# rs485board.net
KiCad netlist of a schematic drawn in EAGLE
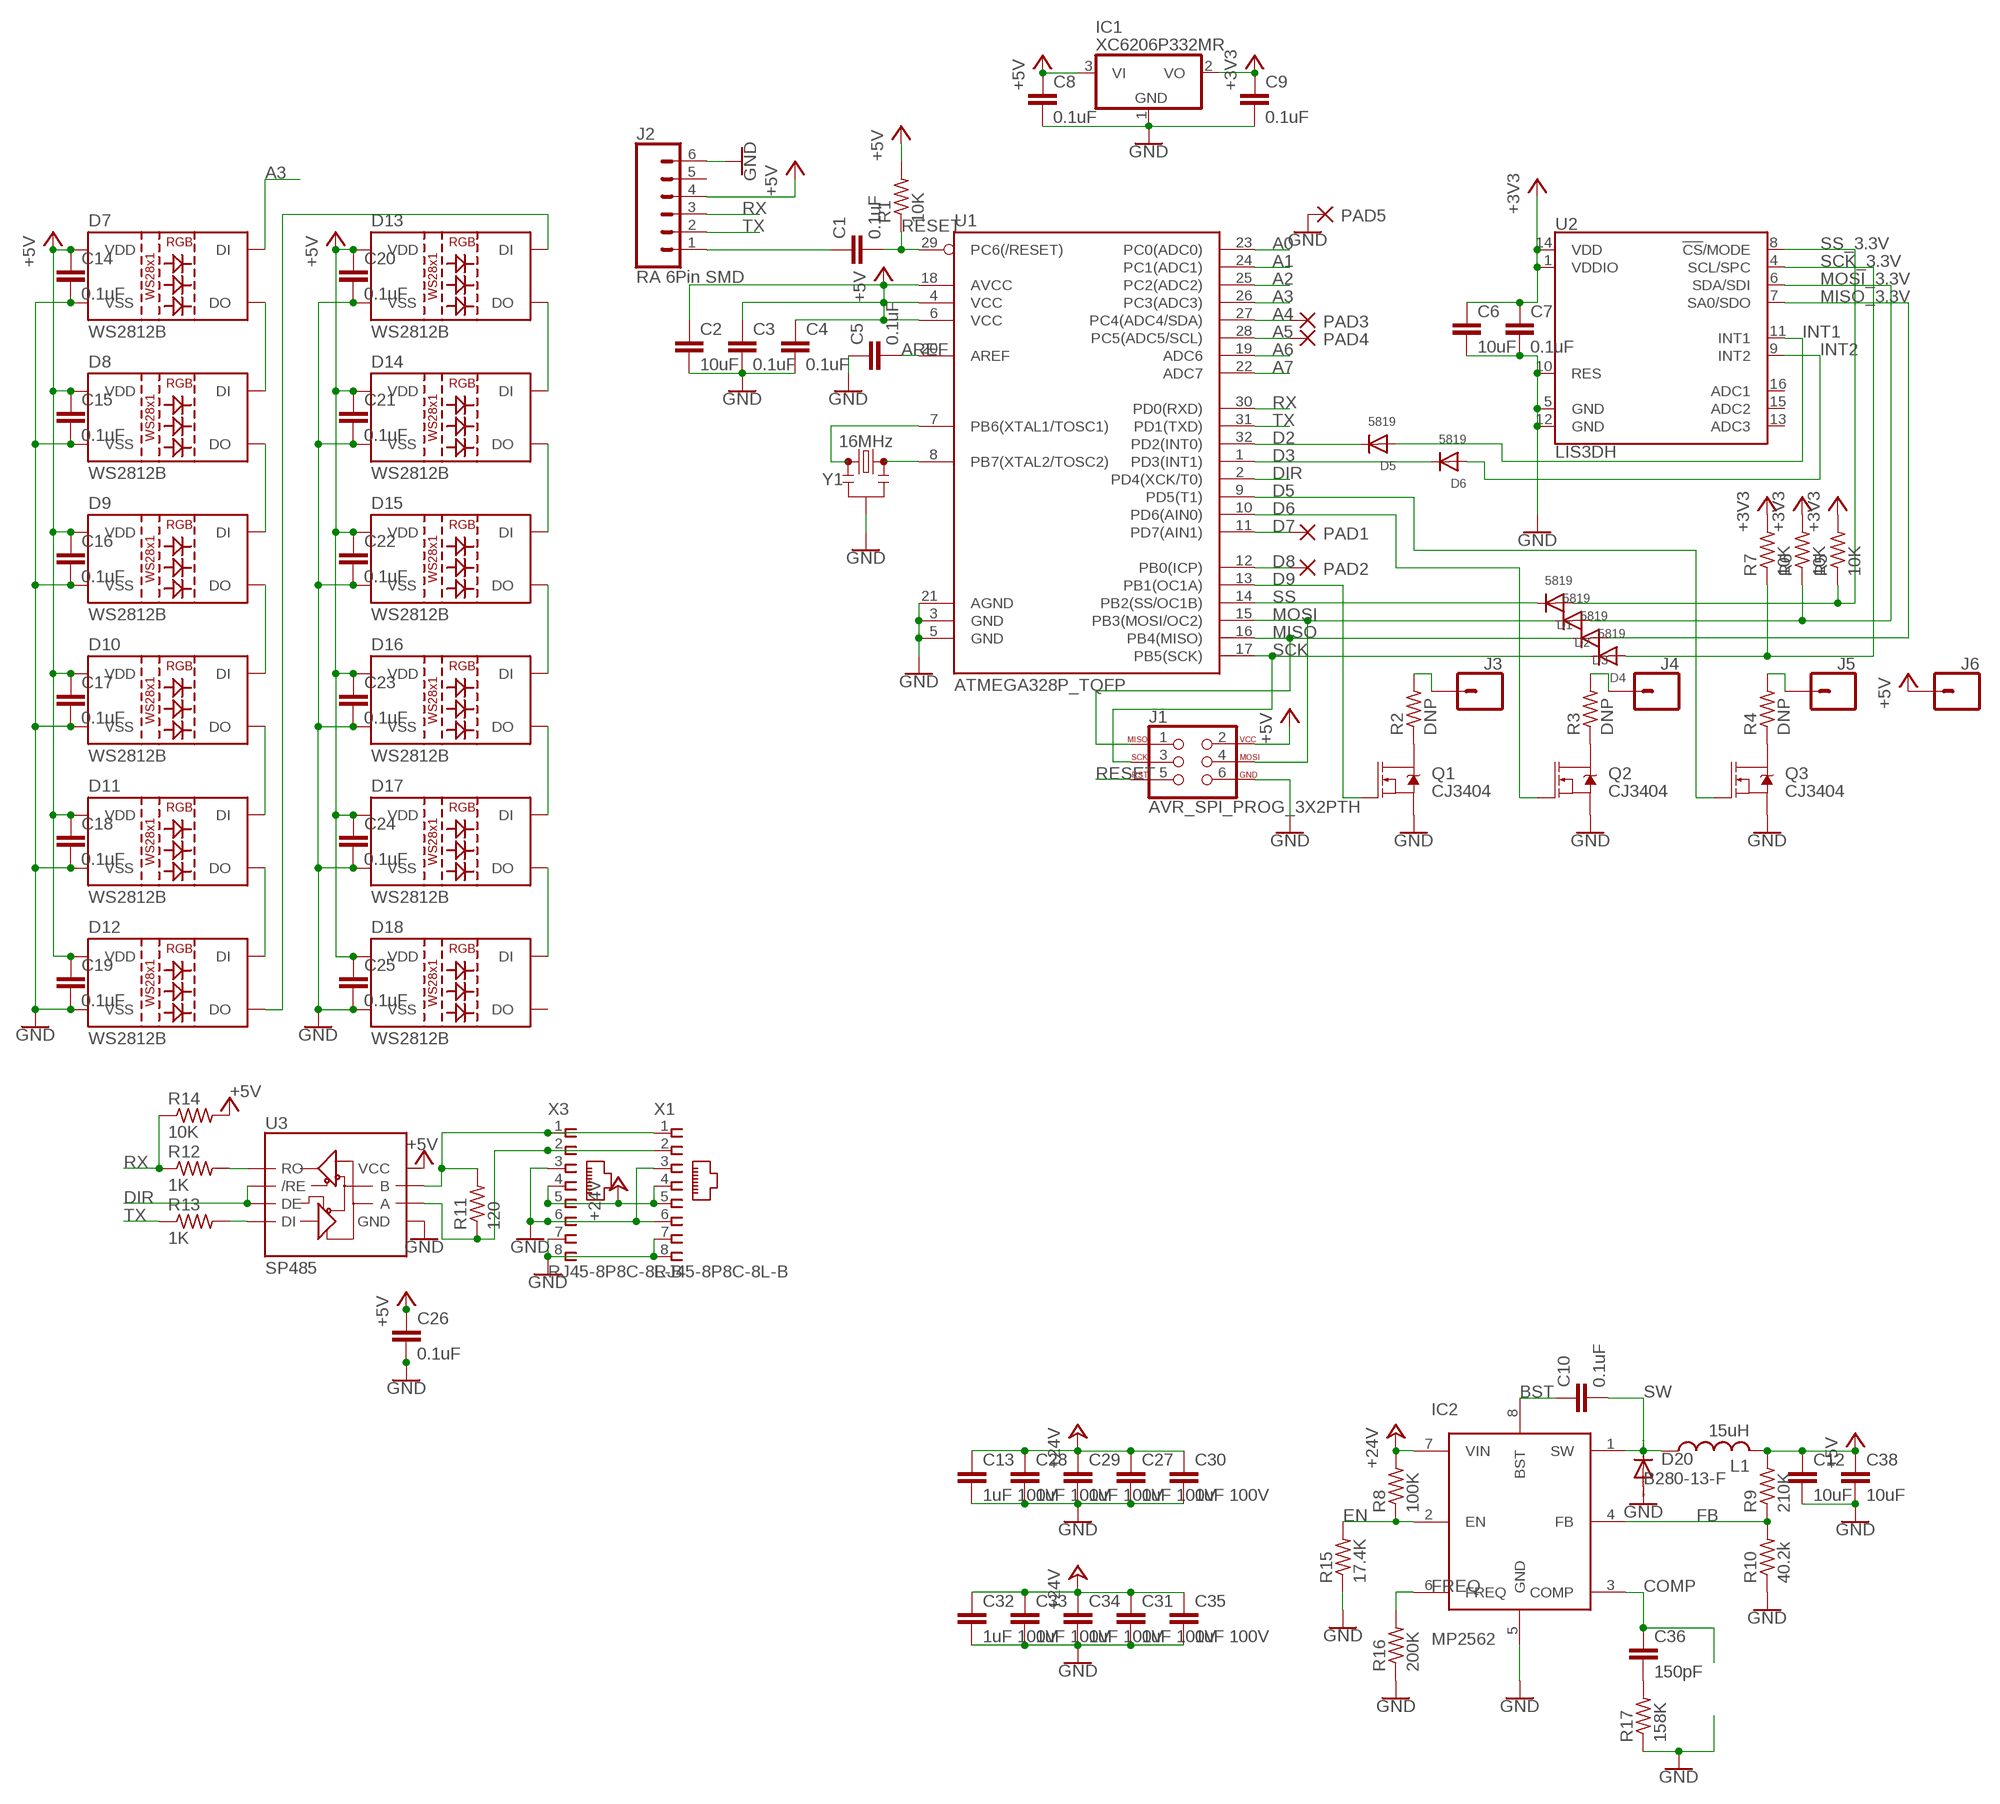
[diagram p0: schematic, sheet 1]

(export (version "E")
  (design (tool "Eeschema 10.0.6"))
  (components
    (comp (ref "C1")
      (value "0.1uF")
      (footprint "eagle-import:C0805K")
      (libsource (lib "eagle-import") (part "C-EUC0805K"))
    )
    (comp (ref "C2")
      (value "10uF")
      (footprint "eagle-import:C0805K")
      (libsource (lib "eagle-import") (part "C-EUC0805K"))
    )
    (comp (ref "C3")
      (value "0.1uF")
      (footprint "eagle-import:C0805K")
      (libsource (lib "eagle-import") (part "C-EUC0805K"))
    )
    (comp (ref "C4")
      (value "0.1uF")
      (footprint "eagle-import:C0805K")
      (libsource (lib "eagle-import") (part "C-EUC0805K"))
    )
    (comp (ref "C5")
      (value "0.1uF")
      (footprint "eagle-import:C0805K")
      (libsource (lib "eagle-import") (part "C-EUC0805K"))
    )
    (comp (ref "C6")
      (value "10uF")
      (footprint "eagle-import:C0805K")
      (libsource (lib "eagle-import") (part "C-EUC0805K"))
    )
    (comp (ref "C7")
      (value "0.1uF")
      (footprint "eagle-import:C0805K")
      (libsource (lib "eagle-import") (part "C-EUC0805K"))
    )
    (comp (ref "C8")
      (value "0.1uF")
      (footprint "eagle-import:C0805K")
      (libsource (lib "eagle-import") (part "C-EUC0805K"))
    )
    (comp (ref "C9")
      (value "0.1uF")
      (footprint "eagle-import:C0805K")
      (libsource (lib "eagle-import") (part "C-EUC0805K"))
    )
    (comp (ref "C10")
      (value "0.1uF")
      (footprint "eagle-import:C0805K")
      (libsource (lib "eagle-import") (part "C-EUC0805K"))
    )
    (comp (ref "C12")
      (value "10uF")
      (footprint "eagle-import:C0805K")
      (libsource (lib "eagle-import") (part "C-EUC0805K"))
    )
    (comp (ref "C13")
      (value "1uF 100V")
      (footprint "eagle-import:1206")
      (libsource (lib "eagle-import") (part "10UF-1206-6.3V-20%"))
    )
    (comp (ref "C14")
      (value "0.1uF")
      (footprint "eagle-import:C0805K")
      (libsource (lib "eagle-import") (part "C-EUC0805K"))
    )
    (comp (ref "C15")
      (value "0.1uF")
      (footprint "eagle-import:C0805K")
      (libsource (lib "eagle-import") (part "C-EUC0805K"))
    )
    (comp (ref "C16")
      (value "0.1uF")
      (footprint "eagle-import:C0805K")
      (libsource (lib "eagle-import") (part "C-EUC0805K"))
    )
    (comp (ref "C17")
      (value "0.1uF")
      (footprint "eagle-import:C0805K")
      (libsource (lib "eagle-import") (part "C-EUC0805K"))
    )
    (comp (ref "C18")
      (value "0.1uF")
      (footprint "eagle-import:C0805K")
      (libsource (lib "eagle-import") (part "C-EUC0805K"))
    )
    (comp (ref "C19")
      (value "0.1uF")
      (footprint "eagle-import:C0805K")
      (libsource (lib "eagle-import") (part "C-EUC0805K"))
    )
    (comp (ref "C20")
      (value "0.1uF")
      (footprint "eagle-import:C0805K")
      (libsource (lib "eagle-import") (part "C-EUC0805K"))
    )
    (comp (ref "C21")
      (value "0.1uF")
      (footprint "eagle-import:C0805K")
      (libsource (lib "eagle-import") (part "C-EUC0805K"))
    )
    (comp (ref "C22")
      (value "0.1uF")
      (footprint "eagle-import:C0805K")
      (libsource (lib "eagle-import") (part "C-EUC0805K"))
    )
    (comp (ref "C23")
      (value "0.1uF")
      (footprint "eagle-import:C0805K")
      (libsource (lib "eagle-import") (part "C-EUC0805K"))
    )
    (comp (ref "C24")
      (value "0.1uF")
      (footprint "eagle-import:C0805K")
      (libsource (lib "eagle-import") (part "C-EUC0805K"))
    )
    (comp (ref "C25")
      (value "0.1uF")
      (footprint "eagle-import:C0805K")
      (libsource (lib "eagle-import") (part "C-EUC0805K"))
    )
    (comp (ref "C26")
      (value "0.1uF")
      (footprint "eagle-import:C0805K")
      (libsource (lib "eagle-import") (part "C-EUC0805K"))
    )
    (comp (ref "C27")
      (value "1uF 100V")
      (footprint "eagle-import:1206")
      (libsource (lib "eagle-import") (part "10UF-1206-6.3V-20%"))
    )
    (comp (ref "C28")
      (value "1uF 100V")
      (footprint "eagle-import:1206")
      (libsource (lib "eagle-import") (part "10UF-1206-6.3V-20%"))
    )
    (comp (ref "C29")
      (value "1uF 100V")
      (footprint "eagle-import:1206")
      (libsource (lib "eagle-import") (part "10UF-1206-6.3V-20%"))
    )
    (comp (ref "C30")
      (value "1uF 100V")
      (footprint "eagle-import:1206")
      (libsource (lib "eagle-import") (part "10UF-1206-6.3V-20%"))
    )
    (comp (ref "C31")
      (value "1uF 100V")
      (footprint "eagle-import:1206")
      (libsource (lib "eagle-import") (part "10UF-1206-6.3V-20%"))
    )
    (comp (ref "C32")
      (value "1uF 100V")
      (footprint "eagle-import:1206")
      (libsource (lib "eagle-import") (part "10UF-1206-6.3V-20%"))
    )
    (comp (ref "C33")
      (value "1uF 100V")
      (footprint "eagle-import:1206")
      (libsource (lib "eagle-import") (part "10UF-1206-6.3V-20%"))
    )
    (comp (ref "C34")
      (value "1uF 100V")
      (footprint "eagle-import:1206")
      (libsource (lib "eagle-import") (part "10UF-1206-6.3V-20%"))
    )
    (comp (ref "C35")
      (value "1uF 100V")
      (footprint "eagle-import:1206")
      (libsource (lib "eagle-import") (part "10UF-1206-6.3V-20%"))
    )
    (comp (ref "C36")
      (value "150pF")
      (footprint "eagle-import:C0805K")
      (libsource (lib "eagle-import") (part "C-EUC0805K"))
    )
    (comp (ref "C38")
      (value "10uF")
      (footprint "eagle-import:C0805K")
      (libsource (lib "eagle-import") (part "C-EUC0805K"))
    )
    (comp (ref "D1")
      (value "5819")
      (footprint "eagle-import:SOD-123")
      (libsource (lib "eagle-import") (part "DIODESOD-123"))
    )
    (comp (ref "D2")
      (value "5819")
      (footprint "eagle-import:SOD-123")
      (libsource (lib "eagle-import") (part "DIODESOD-123"))
    )
    (comp (ref "D3")
      (value "5819")
      (footprint "eagle-import:SOD-123")
      (libsource (lib "eagle-import") (part "DIODESOD-123"))
    )
    (comp (ref "D4")
      (value "5819")
      (footprint "eagle-import:SOD-123")
      (libsource (lib "eagle-import") (part "DIODESOD-123"))
    )
    (comp (ref "D5")
      (value "5819")
      (footprint "eagle-import:SOD-123")
      (libsource (lib "eagle-import") (part "DIODESOD-123"))
    )
    (comp (ref "D6")
      (value "5819")
      (footprint "eagle-import:SOD-123")
      (libsource (lib "eagle-import") (part "DIODESOD-123"))
    )
    (comp (ref "D7")
      (value "WS2812B")
      (footprint "eagle-import:WS2812B")
      (libsource (lib "eagle-import") (part "WS2812B"))
    )
    (comp (ref "D8")
      (value "WS2812B")
      (footprint "eagle-import:WS2812B")
      (libsource (lib "eagle-import") (part "WS2812B"))
    )
    (comp (ref "D9")
      (value "WS2812B")
      (footprint "eagle-import:WS2812B")
      (libsource (lib "eagle-import") (part "WS2812B"))
    )
    (comp (ref "D10")
      (value "WS2812B")
      (footprint "eagle-import:WS2812B")
      (libsource (lib "eagle-import") (part "WS2812B"))
    )
    (comp (ref "D11")
      (value "WS2812B")
      (footprint "eagle-import:WS2812B")
      (libsource (lib "eagle-import") (part "WS2812B"))
    )
    (comp (ref "D12")
      (value "WS2812B")
      (footprint "eagle-import:WS2812B")
      (libsource (lib "eagle-import") (part "WS2812B"))
    )
    (comp (ref "D13")
      (value "WS2812B")
      (footprint "eagle-import:WS2812B")
      (libsource (lib "eagle-import") (part "WS2812B"))
    )
    (comp (ref "D14")
      (value "WS2812B")
      (footprint "eagle-import:WS2812B")
      (libsource (lib "eagle-import") (part "WS2812B"))
    )
    (comp (ref "D15")
      (value "WS2812B")
      (footprint "eagle-import:WS2812B")
      (libsource (lib "eagle-import") (part "WS2812B"))
    )
    (comp (ref "D16")
      (value "WS2812B")
      (footprint "eagle-import:WS2812B")
      (libsource (lib "eagle-import") (part "WS2812B"))
    )
    (comp (ref "D17")
      (value "WS2812B")
      (footprint "eagle-import:WS2812B")
      (libsource (lib "eagle-import") (part "WS2812B"))
    )
    (comp (ref "D18")
      (value "WS2812B")
      (footprint "eagle-import:WS2812B")
      (libsource (lib "eagle-import") (part "WS2812B"))
    )
    (comp (ref "D20")
      (value "B280-13-F")
      (footprint "eagle-import:DO214AA")
      (libsource (lib "eagle-import") (part "DIODE-DO214AA"))
    )
    (comp (ref "IC1")
      (value "XC6206P332MR")
      (footprint "eagle-import:SOT23")
      (libsource (lib "eagle-import") (part "MCP1703CB"))
    )
    (comp (ref "IC2")
      (value "MP2562")
      (footprint "eagle-import:SO08")
      (libsource (lib "eagle-import") (part "MP2562"))
    )
    (comp (ref "J1")
      (value "AVR_SPI_PROG_3X2PTH")
      (footprint "eagle-import:2X3")
      (libsource (lib "eagle-import") (part "AVR_SPI_PROG_3X2PTH"))
    )
    (comp (ref "J2")
      (value "RA 6Pin SMD")
      (footprint "eagle-import:1X06-SMD_RA_MALE")
      (libsource (lib "eagle-import") (part "CONN_06SMD"))
    )
    (comp (ref "J3")
      (value "CONN_01")
      (footprint "eagle-import:1X01")
      (libsource (lib "eagle-import") (part "CONN_01"))
    )
    (comp (ref "J4")
      (value "CONN_01")
      (footprint "eagle-import:1X01")
      (libsource (lib "eagle-import") (part "CONN_01"))
    )
    (comp (ref "J5")
      (value "CONN_01")
      (footprint "eagle-import:1X01")
      (libsource (lib "eagle-import") (part "CONN_01"))
    )
    (comp (ref "J6")
      (value "CONN_01")
      (footprint "eagle-import:1X01")
      (libsource (lib "eagle-import") (part "CONN_01"))
    )
    (comp (ref "L1")
      (value "15uH")
      (footprint "eagle-import:SLF12575")
      (libsource (lib "eagle-import") (part "SLF12575T"))
    )
    (comp (ref "PAD1")
      (value "1,6/0,8")
      (footprint "eagle-import:1,6_0,8")
      (libsource (lib "eagle-import") (part "1,6/0,8"))
    )
    (comp (ref "PAD2")
      (value "1,6/0,8")
      (footprint "eagle-import:1,6_0,8")
      (libsource (lib "eagle-import") (part "1,6/0,8"))
    )
    (comp (ref "PAD3")
      (value "1,6/0,8")
      (footprint "eagle-import:1,6_0,8")
      (libsource (lib "eagle-import") (part "1,6/0,8"))
    )
    (comp (ref "PAD4")
      (value "1,6/0,8")
      (footprint "eagle-import:1,6_0,8")
      (libsource (lib "eagle-import") (part "1,6/0,8"))
    )
    (comp (ref "PAD5")
      (value "1,6/0,8")
      (footprint "eagle-import:1,6_0,8")
      (libsource (lib "eagle-import") (part "1,6/0,8"))
    )
    (comp (ref "Q1")
      (value "CJ3404")
      (footprint "eagle-import:SOT23-3")
      (libsource (lib "eagle-import") (part "MOSFET-NCH-AO3404A"))
    )
    (comp (ref "Q2")
      (value "CJ3404")
      (footprint "eagle-import:SOT23-3")
      (libsource (lib "eagle-import") (part "MOSFET-NCH-AO3404A"))
    )
    (comp (ref "Q3")
      (value "CJ3404")
      (footprint "eagle-import:SOT23-3")
      (libsource (lib "eagle-import") (part "MOSFET-NCH-AO3404A"))
    )
    (comp (ref "R1")
      (value "10K")
      (footprint "eagle-import:R0805")
      (libsource (lib "eagle-import") (part "R-US_R0805"))
    )
    (comp (ref "R2")
      (value "DNP")
      (footprint "eagle-import:R0805")
      (libsource (lib "eagle-import") (part "R-US_R0805"))
    )
    (comp (ref "R3")
      (value "DNP")
      (footprint "eagle-import:R0805")
      (libsource (lib "eagle-import") (part "R-US_R0805"))
    )
    (comp (ref "R4")
      (value "DNP")
      (footprint "eagle-import:R0805")
      (libsource (lib "eagle-import") (part "R-US_R0805"))
    )
    (comp (ref "R5")
      (value "10K")
      (footprint "eagle-import:R0805")
      (libsource (lib "eagle-import") (part "R-US_R0805"))
    )
    (comp (ref "R6")
      (value "10K")
      (footprint "eagle-import:R0805")
      (libsource (lib "eagle-import") (part "R-US_R0805"))
    )
    (comp (ref "R7")
      (value "10K")
      (footprint "eagle-import:R0805")
      (libsource (lib "eagle-import") (part "R-US_R0805"))
    )
    (comp (ref "R8")
      (value "100K")
      (footprint "eagle-import:R0805")
      (libsource (lib "eagle-import") (part "R-US_R0805"))
    )
    (comp (ref "R9")
      (value "210K")
      (footprint "eagle-import:R0805")
      (libsource (lib "eagle-import") (part "R-US_R0805"))
    )
    (comp (ref "R10")
      (value "40.2k")
      (footprint "eagle-import:R0805")
      (libsource (lib "eagle-import") (part "R-US_R0805"))
    )
    (comp (ref "R11")
      (value "120")
      (footprint "eagle-import:R0805")
      (libsource (lib "eagle-import") (part "R-US_R0805"))
    )
    (comp (ref "R12")
      (value "1K")
      (footprint "eagle-import:R0805")
      (libsource (lib "eagle-import") (part "R-US_R0805"))
    )
    (comp (ref "R13")
      (value "1K")
      (footprint "eagle-import:R0805")
      (libsource (lib "eagle-import") (part "R-US_R0805"))
    )
    (comp (ref "R14")
      (value "10K")
      (footprint "eagle-import:R0805")
      (libsource (lib "eagle-import") (part "R-US_R0805"))
    )
    (comp (ref "R15")
      (value "17.4K")
      (footprint "eagle-import:R0805")
      (libsource (lib "eagle-import") (part "R-US_R0805"))
    )
    (comp (ref "R16")
      (value "200K")
      (footprint "eagle-import:R0805")
      (libsource (lib "eagle-import") (part "R-US_R0805"))
    )
    (comp (ref "R17")
      (value "158K")
      (footprint "eagle-import:R0805")
      (libsource (lib "eagle-import") (part "R-US_R0805"))
    )
    (comp (ref "U1")
      (value "ATMEGA328P_TQFP")
      (footprint "eagle-import:TQFP32-08")
      (libsource (lib "eagle-import") (part "ATMEGA328P_TQFP"))
    )
    (comp (ref "U2")
      (value "LIS3DH")
      (footprint "eagle-import:LGA-16-3X3")
      (libsource (lib "eagle-import") (part "LIS3DH"))
    )
    (comp (ref "U3")
      (value "SP485")
      (footprint "eagle-import:SO08")
      (libsource (lib "eagle-import") (part "RS485SOIC"))
    )
    (comp (ref "X1")
      (value "RJ45-8P8C-8L-B")
      (footprint "eagle-import:RJ45-SHIELD-DS1128-S80BP")
      (fields (field (name "MF") "TYCO ELECTRONICS") (field (name "MPN") "RJ45-8L-B"))
      (libsource (lib "eagle-import") (part "RJ45-8P8C-8L-B"))
    )
    (comp (ref "X3")
      (value "RJ45-8P8C-8L-B")
      (footprint "eagle-import:RJ45-SHIELD-DS1128-S80BP")
      (fields (field (name "MF") "TYCO ELECTRONICS") (field (name "MPN") "RJ45-8L-B"))
      (libsource (lib "eagle-import") (part "RJ45-8P8C-8L-B"))
    )
    (comp (ref "Y1")
      (value "16MHz")
      (footprint "eagle-import:RESONATOR-SMD-3.2X1.3")
      (libsource (lib "eagle-import") (part "RESONATOR-16MHZSMD_3.2X1.3"))
    )
  )
  (nets
    (net (code "1") (name "+3V3") (class "Default")
      (node (ref "C6") (pin "1") (pinfunction "1_1") (pintype "passive"))
      (node (ref "C7") (pin "1") (pinfunction "1_1") (pintype "passive"))
      (node (ref "C9") (pin "1") (pinfunction "1_1") (pintype "passive"))
      (node (ref "IC1") (pin "2") (pinfunction "VO_2") (pintype "passive"))
      (node (ref "R5") (pin "2") (pinfunction "2_2") (pintype "passive"))
      (node (ref "R6") (pin "2") (pinfunction "2_2") (pintype "passive"))
      (node (ref "R7") (pin "2") (pinfunction "2_2") (pintype "passive"))
      (node (ref "U2") (pin "1") (pinfunction "VDDIO_1") (pintype "bidirectional"))
      (node (ref "U2") (pin "14") (pinfunction "VDD_14") (pintype "bidirectional"))
    )
    (net (code "2") (name "+5V") (class "Default")
      (node (ref "C12") (pin "1") (pinfunction "1_1") (pintype "passive"))
      (node (ref "C14") (pin "1") (pinfunction "1_1") (pintype "passive"))
      (node (ref "C15") (pin "1") (pinfunction "1_1") (pintype "passive"))
      (node (ref "C16") (pin "1") (pinfunction "1_1") (pintype "passive"))
      (node (ref "C17") (pin "1") (pinfunction "1_1") (pintype "passive"))
      (node (ref "C18") (pin "1") (pinfunction "1_1") (pintype "passive"))
      (node (ref "C19") (pin "1") (pinfunction "1_1") (pintype "passive"))
      (node (ref "C2") (pin "1") (pinfunction "1_1") (pintype "passive"))
      (node (ref "C20") (pin "1") (pinfunction "1_1") (pintype "passive"))
      (node (ref "C21") (pin "1") (pinfunction "1_1") (pintype "passive"))
      (node (ref "C22") (pin "1") (pinfunction "1_1") (pintype "passive"))
      (node (ref "C23") (pin "1") (pinfunction "1_1") (pintype "passive"))
      (node (ref "C24") (pin "1") (pinfunction "1_1") (pintype "passive"))
      (node (ref "C25") (pin "1") (pinfunction "1_1") (pintype "passive"))
      (node (ref "C26") (pin "1") (pinfunction "1_1") (pintype "passive"))
      (node (ref "C3") (pin "1") (pinfunction "1_1") (pintype "passive"))
      (node (ref "C38") (pin "1") (pinfunction "1_1") (pintype "passive"))
      (node (ref "C4") (pin "1") (pinfunction "1_1") (pintype "passive"))
      (node (ref "C8") (pin "1") (pinfunction "1_1") (pintype "passive"))
      (node (ref "D10") (pin "1") (pinfunction "VDD_1") (pintype "bidirectional"))
      (node (ref "D11") (pin "1") (pinfunction "VDD_1") (pintype "bidirectional"))
      (node (ref "D12") (pin "1") (pinfunction "VDD_1") (pintype "bidirectional"))
      (node (ref "D13") (pin "1") (pinfunction "VDD_1") (pintype "bidirectional"))
      (node (ref "D14") (pin "1") (pinfunction "VDD_1") (pintype "bidirectional"))
      (node (ref "D15") (pin "1") (pinfunction "VDD_1") (pintype "bidirectional"))
      (node (ref "D16") (pin "1") (pinfunction "VDD_1") (pintype "bidirectional"))
      (node (ref "D17") (pin "1") (pinfunction "VDD_1") (pintype "bidirectional"))
      (node (ref "D18") (pin "1") (pinfunction "VDD_1") (pintype "bidirectional"))
      (node (ref "D7") (pin "1") (pinfunction "VDD_1") (pintype "bidirectional"))
      (node (ref "D8") (pin "1") (pinfunction "VDD_1") (pintype "bidirectional"))
      (node (ref "D9") (pin "1") (pinfunction "VDD_1") (pintype "bidirectional"))
      (node (ref "IC1") (pin "3") (pinfunction "VI_3") (pintype "input"))
      (node (ref "J1") (pin "2") (pinfunction "2_2") (pintype "passive"))
      (node (ref "J2") (pin "4") (pinfunction "4_4") (pintype "passive"))
      (node (ref "J6") (pin "1") (pinfunction "1_1") (pintype "passive"))
      (node (ref "L1") (pin "P$2") (pinfunction "2_P$2") (pintype "passive"))
      (node (ref "R1") (pin "2") (pinfunction "2_2") (pintype "passive"))
      (node (ref "R14") (pin "2") (pinfunction "2_2") (pintype "passive"))
      (node (ref "R9") (pin "2") (pinfunction "2_2") (pintype "passive"))
      (node (ref "U1") (pin "18") (pinfunction "AVCC_18") (pintype "bidirectional"))
      (node (ref "U1") (pin "4") (pinfunction "VCC_4") (pintype "bidirectional"))
      (node (ref "U1") (pin "6") (pinfunction "VCC_6") (pintype "bidirectional"))
      (node (ref "U3") (pin "8") (pinfunction "VCC_8") (pintype "bidirectional"))
    )
    (net (code "3") (name "+24V") (class "Default")
      (node (ref "C13") (pin "1") (pinfunction "1_1") (pintype "passive"))
      (node (ref "C27") (pin "1") (pinfunction "1_1") (pintype "passive"))
      (node (ref "C28") (pin "1") (pinfunction "1_1") (pintype "passive"))
      (node (ref "C29") (pin "1") (pinfunction "1_1") (pintype "passive"))
      (node (ref "C30") (pin "1") (pinfunction "1_1") (pintype "passive"))
      (node (ref "C31") (pin "1") (pinfunction "1_1") (pintype "passive"))
      (node (ref "C32") (pin "1") (pinfunction "1_1") (pintype "passive"))
      (node (ref "C33") (pin "1") (pinfunction "1_1") (pintype "passive"))
      (node (ref "C34") (pin "1") (pinfunction "1_1") (pintype "passive"))
      (node (ref "C35") (pin "1") (pinfunction "1_1") (pintype "passive"))
      (node (ref "IC2") (pin "7") (pinfunction "VIN_7") (pintype "bidirectional"))
      (node (ref "R8") (pin "2") (pinfunction "2_2") (pintype "passive"))
      (node (ref "X1") (pin "4") (pinfunction "4_4") (pintype "passive"))
      (node (ref "X1") (pin "5") (pinfunction "5_5") (pintype "passive"))
      (node (ref "X3") (pin "4") (pinfunction "4_4") (pintype "passive"))
      (node (ref "X3") (pin "5") (pinfunction "5_5") (pintype "passive"))
    )
    (net (code "4") (name "/A0") (class "Default")
      (node (ref "U1") (pin "23") (pinfunction "PC0(ADC0)_23") (pintype "bidirectional"))
    )
    (net (code "5") (name "/A1") (class "Default")
      (node (ref "U1") (pin "24") (pinfunction "PC1(ADC1)_24") (pintype "bidirectional"))
    )
    (net (code "6") (name "/A2") (class "Default")
      (node (ref "U1") (pin "25") (pinfunction "PC2(ADC2)_25") (pintype "bidirectional"))
    )
    (net (code "7") (name "/A3") (class "Default")
      (node (ref "D7") (pin "4") (pinfunction "DI_4") (pintype "bidirectional"))
      (node (ref "U1") (pin "26") (pinfunction "PC3(ADC3)_26") (pintype "bidirectional"))
    )
    (net (code "8") (name "/A4") (class "Default")
      (node (ref "PAD3") (pin "1") (pinfunction "P_1") (pintype "passive"))
      (node (ref "U1") (pin "27") (pinfunction "PC4(ADC4/SDA)_27") (pintype "bidirectional"))
    )
    (net (code "9") (name "/A5") (class "Default")
      (node (ref "PAD4") (pin "1") (pinfunction "P_1") (pintype "passive"))
      (node (ref "U1") (pin "28") (pinfunction "PC5(ADC5/SCL)_28") (pintype "bidirectional"))
    )
    (net (code "10") (name "/A6") (class "Default")
      (node (ref "U1") (pin "19") (pinfunction "ADC6_19") (pintype "bidirectional"))
    )
    (net (code "11") (name "/A7") (class "Default")
      (node (ref "U1") (pin "22") (pinfunction "ADC7_22") (pintype "bidirectional"))
    )
    (net (code "12") (name "/AREF") (class "Default")
      (node (ref "C5") (pin "2") (pinfunction "2_2") (pintype "passive"))
      (node (ref "U1") (pin "20") (pinfunction "AREF_20") (pintype "bidirectional"))
    )
    (net (code "13") (name "/BST") (class "Default")
      (node (ref "C10") (pin "1") (pinfunction "1_1") (pintype "passive"))
      (node (ref "IC2") (pin "8") (pinfunction "BST_8") (pintype "bidirectional"))
    )
    (net (code "14") (name "/COMP") (class "Default")
      (node (ref "C36") (pin "1") (pinfunction "1_1") (pintype "passive"))
      (node (ref "IC2") (pin "3") (pinfunction "COMP_3") (pintype "bidirectional"))
    )
    (net (code "15") (name "/D2") (class "Default")
      (node (ref "D5") (pin "C") (pinfunction "C_C") (pintype "passive"))
      (node (ref "U1") (pin "32") (pinfunction "PD2(INT0)_32") (pintype "bidirectional"))
    )
    (net (code "16") (name "/D3") (class "Default")
      (node (ref "D6") (pin "C") (pinfunction "C_C") (pintype "passive"))
      (node (ref "U1") (pin "1") (pinfunction "PD3(INT1)_1") (pintype "bidirectional"))
    )
    (net (code "17") (name "/D5") (class "Default")
      (node (ref "Q3") (pin "1") (pinfunction "G_1") (pintype "bidirectional"))
      (node (ref "U1") (pin "9") (pinfunction "PD5(T1)_9") (pintype "bidirectional"))
    )
    (net (code "18") (name "/D6") (class "Default")
      (node (ref "Q2") (pin "1") (pinfunction "G_1") (pintype "bidirectional"))
      (node (ref "U1") (pin "10") (pinfunction "PD6(AIN0)_10") (pintype "bidirectional"))
    )
    (net (code "19") (name "/D7") (class "Default")
      (node (ref "PAD1") (pin "1") (pinfunction "P_1") (pintype "passive"))
      (node (ref "U1") (pin "11") (pinfunction "PD7(AIN1)_11") (pintype "bidirectional"))
    )
    (net (code "20") (name "/D8") (class "Default")
      (node (ref "PAD2") (pin "1") (pinfunction "P_1") (pintype "passive"))
      (node (ref "U1") (pin "12") (pinfunction "PB0(ICP)_12") (pintype "bidirectional"))
    )
    (net (code "21") (name "/D9") (class "Default")
      (node (ref "Q1") (pin "1") (pinfunction "G_1") (pintype "bidirectional"))
      (node (ref "U1") (pin "13") (pinfunction "PB1(OC1A)_13") (pintype "bidirectional"))
    )
    (net (code "22") (name "/DIR") (class "Default")
      (node (ref "U1") (pin "2") (pinfunction "PD4(XCK/T0)_2") (pintype "bidirectional"))
      (node (ref "U3") (pin "2") (pinfunction "/RE_2") (pintype "bidirectional"))
      (node (ref "U3") (pin "3") (pinfunction "DE_3") (pintype "bidirectional"))
    )
    (net (code "23") (name "/EN") (class "Default")
      (node (ref "IC2") (pin "2") (pinfunction "EN_2") (pintype "bidirectional"))
      (node (ref "R15") (pin "2") (pinfunction "2_2") (pintype "passive"))
      (node (ref "R8") (pin "1") (pinfunction "1_1") (pintype "passive"))
    )
    (net (code "24") (name "/FB") (class "Default")
      (node (ref "IC2") (pin "4") (pinfunction "FB_4") (pintype "bidirectional"))
      (node (ref "R10") (pin "2") (pinfunction "2_2") (pintype "passive"))
      (node (ref "R9") (pin "1") (pinfunction "1_1") (pintype "passive"))
    )
    (net (code "25") (name "/FREQ") (class "Default")
      (node (ref "IC2") (pin "6") (pinfunction "FREQ_6") (pintype "bidirectional"))
      (node (ref "R16") (pin "2") (pinfunction "2_2") (pintype "passive"))
    )
    (net (code "26") (name "/INT1") (class "Default")
      (node (ref "D5") (pin "A") (pinfunction "A_A") (pintype "passive"))
      (node (ref "U2") (pin "11") (pinfunction "INT1_11") (pintype "bidirectional"))
    )
    (net (code "27") (name "/INT2") (class "Default")
      (node (ref "D6") (pin "A") (pinfunction "A_A") (pintype "passive"))
      (node (ref "U2") (pin "9") (pinfunction "INT2_9") (pintype "bidirectional"))
    )
    (net (code "28") (name "/MISO") (class "Default")
      (node (ref "D3") (pin "C") (pinfunction "C_C") (pintype "passive"))
      (node (ref "J1") (pin "1") (pinfunction "1_1") (pintype "passive"))
      (node (ref "U1") (pin "16") (pinfunction "PB4(MISO)_16") (pintype "bidirectional"))
    )
    (net (code "29") (name "/MISO_3.3V") (class "Default")
      (node (ref "D3") (pin "A") (pinfunction "A_A") (pintype "passive"))
      (node (ref "U2") (pin "7") (pinfunction "SA0/SDO_7") (pintype "bidirectional"))
    )
    (net (code "30") (name "/MOSI") (class "Default")
      (node (ref "D2") (pin "C") (pinfunction "C_C") (pintype "passive"))
      (node (ref "J1") (pin "4") (pinfunction "4_4") (pintype "passive"))
      (node (ref "U1") (pin "15") (pinfunction "PB3(MOSI/OC2)_15") (pintype "bidirectional"))
    )
    (net (code "31") (name "/MOSI_3.3V") (class "Default")
      (node (ref "D2") (pin "A") (pinfunction "A_A") (pintype "passive"))
      (node (ref "R6") (pin "1") (pinfunction "1_1") (pintype "passive"))
      (node (ref "U2") (pin "6") (pinfunction "SDA/SDI_6") (pintype "bidirectional"))
    )
    (net (code "32") (name "/RESET") (class "Default")
      (node (ref "C1") (pin "2") (pinfunction "2_2") (pintype "passive"))
      (node (ref "J1") (pin "5") (pinfunction "5_5") (pintype "passive"))
      (node (ref "R1") (pin "1") (pinfunction "1_1") (pintype "passive"))
      (node (ref "U1") (pin "29") (pinfunction "PC6(/RESET)_29") (pintype "bidirectional"))
    )
    (net (code "33") (name "/RX") (class "Default")
      (node (ref "J2") (pin "3") (pinfunction "3_3") (pintype "passive"))
      (node (ref "R12") (pin "1") (pinfunction "1_1") (pintype "passive"))
      (node (ref "R14") (pin "1") (pinfunction "1_1") (pintype "passive"))
      (node (ref "U1") (pin "30") (pinfunction "PD0(RXD)_30") (pintype "bidirectional"))
    )
    (net (code "34") (name "/SCK") (class "Default")
      (node (ref "D4") (pin "C") (pinfunction "C_C") (pintype "passive"))
      (node (ref "J1") (pin "3") (pinfunction "3_3") (pintype "passive"))
      (node (ref "U1") (pin "17") (pinfunction "PB5(SCK)_17") (pintype "bidirectional"))
    )
    (net (code "35") (name "/SCK_3.3V") (class "Default")
      (node (ref "D4") (pin "A") (pinfunction "A_A") (pintype "passive"))
      (node (ref "R7") (pin "1") (pinfunction "1_1") (pintype "passive"))
      (node (ref "U2") (pin "4") (pinfunction "SCL/SPC_4") (pintype "bidirectional"))
    )
    (net (code "36") (name "/SS") (class "Default")
      (node (ref "D1") (pin "C") (pinfunction "C_C") (pintype "passive"))
      (node (ref "U1") (pin "14") (pinfunction "PB2(SS/OC1B)_14") (pintype "bidirectional"))
    )
    (net (code "37") (name "/SS_3.3V") (class "Default")
      (node (ref "D1") (pin "A") (pinfunction "A_A") (pintype "passive"))
      (node (ref "R5") (pin "1") (pinfunction "1_1") (pintype "passive"))
      (node (ref "U2") (pin "8") (pinfunction "~{CS}/MODE_8") (pintype "bidirectional"))
    )
    (net (code "38") (name "/SW") (class "Default")
      (node (ref "C10") (pin "2") (pinfunction "2_2") (pintype "passive"))
      (node (ref "D20") (pin "C") (pinfunction "C_C") (pintype "passive"))
      (node (ref "IC2") (pin "1") (pinfunction "SW_1") (pintype "bidirectional"))
      (node (ref "L1") (pin "P$1") (pinfunction "1_P$1") (pintype "passive"))
    )
    (net (code "39") (name "/TX") (class "Default")
      (node (ref "J2") (pin "2") (pinfunction "2_2") (pintype "passive"))
      (node (ref "R13") (pin "1") (pinfunction "1_1") (pintype "passive"))
      (node (ref "U1") (pin "31") (pinfunction "PD1(TXD)_31") (pintype "bidirectional"))
    )
    (net (code "40") (name "GND") (class "Default")
      (node (ref "C12") (pin "2") (pinfunction "2_2") (pintype "passive"))
      (node (ref "C13") (pin "2") (pinfunction "2_2") (pintype "passive"))
      (node (ref "C14") (pin "2") (pinfunction "2_2") (pintype "passive"))
      (node (ref "C15") (pin "2") (pinfunction "2_2") (pintype "passive"))
      (node (ref "C16") (pin "2") (pinfunction "2_2") (pintype "passive"))
      (node (ref "C17") (pin "2") (pinfunction "2_2") (pintype "passive"))
      (node (ref "C18") (pin "2") (pinfunction "2_2") (pintype "passive"))
      (node (ref "C19") (pin "2") (pinfunction "2_2") (pintype "passive"))
      (node (ref "C2") (pin "2") (pinfunction "2_2") (pintype "passive"))
      (node (ref "C20") (pin "2") (pinfunction "2_2") (pintype "passive"))
      (node (ref "C21") (pin "2") (pinfunction "2_2") (pintype "passive"))
      (node (ref "C22") (pin "2") (pinfunction "2_2") (pintype "passive"))
      (node (ref "C23") (pin "2") (pinfunction "2_2") (pintype "passive"))
      (node (ref "C24") (pin "2") (pinfunction "2_2") (pintype "passive"))
      (node (ref "C25") (pin "2") (pinfunction "2_2") (pintype "passive"))
      (node (ref "C26") (pin "2") (pinfunction "2_2") (pintype "passive"))
      (node (ref "C27") (pin "2") (pinfunction "2_2") (pintype "passive"))
      (node (ref "C28") (pin "2") (pinfunction "2_2") (pintype "passive"))
      (node (ref "C29") (pin "2") (pinfunction "2_2") (pintype "passive"))
      (node (ref "C3") (pin "2") (pinfunction "2_2") (pintype "passive"))
      (node (ref "C30") (pin "2") (pinfunction "2_2") (pintype "passive"))
      (node (ref "C31") (pin "2") (pinfunction "2_2") (pintype "passive"))
      (node (ref "C32") (pin "2") (pinfunction "2_2") (pintype "passive"))
      (node (ref "C33") (pin "2") (pinfunction "2_2") (pintype "passive"))
      (node (ref "C34") (pin "2") (pinfunction "2_2") (pintype "passive"))
      (node (ref "C35") (pin "2") (pinfunction "2_2") (pintype "passive"))
      (node (ref "C38") (pin "2") (pinfunction "2_2") (pintype "passive"))
      (node (ref "C4") (pin "2") (pinfunction "2_2") (pintype "passive"))
      (node (ref "C5") (pin "1") (pinfunction "1_1") (pintype "passive"))
      (node (ref "C6") (pin "2") (pinfunction "2_2") (pintype "passive"))
      (node (ref "C7") (pin "2") (pinfunction "2_2") (pintype "passive"))
      (node (ref "C8") (pin "2") (pinfunction "2_2") (pintype "passive"))
      (node (ref "C9") (pin "2") (pinfunction "2_2") (pintype "passive"))
      (node (ref "D10") (pin "3") (pinfunction "VSS_3") (pintype "bidirectional"))
      (node (ref "D11") (pin "3") (pinfunction "VSS_3") (pintype "bidirectional"))
      (node (ref "D12") (pin "3") (pinfunction "VSS_3") (pintype "bidirectional"))
      (node (ref "D13") (pin "3") (pinfunction "VSS_3") (pintype "bidirectional"))
      (node (ref "D14") (pin "3") (pinfunction "VSS_3") (pintype "bidirectional"))
      (node (ref "D15") (pin "3") (pinfunction "VSS_3") (pintype "bidirectional"))
      (node (ref "D16") (pin "3") (pinfunction "VSS_3") (pintype "bidirectional"))
      (node (ref "D17") (pin "3") (pinfunction "VSS_3") (pintype "bidirectional"))
      (node (ref "D18") (pin "3") (pinfunction "VSS_3") (pintype "bidirectional"))
      (node (ref "D20") (pin "A") (pinfunction "A_A") (pintype "passive"))
      (node (ref "D7") (pin "3") (pinfunction "VSS_3") (pintype "bidirectional"))
      (node (ref "D8") (pin "3") (pinfunction "VSS_3") (pintype "bidirectional"))
      (node (ref "D9") (pin "3") (pinfunction "VSS_3") (pintype "bidirectional"))
      (node (ref "IC1") (pin "1") (pinfunction "GND_1") (pintype "passive"))
      (node (ref "IC2") (pin "5") (pinfunction "GND_5") (pintype "bidirectional"))
      (node (ref "J1") (pin "6") (pinfunction "6_6") (pintype "passive"))
      (node (ref "J2") (pin "6") (pinfunction "6_6") (pintype "passive"))
      (node (ref "PAD5") (pin "1") (pinfunction "P_1") (pintype "passive"))
      (node (ref "Q1") (pin "2") (pinfunction "S_2") (pintype "bidirectional"))
      (node (ref "Q2") (pin "2") (pinfunction "S_2") (pintype "bidirectional"))
      (node (ref "Q3") (pin "2") (pinfunction "S_2") (pintype "bidirectional"))
      (node (ref "R10") (pin "1") (pinfunction "1_1") (pintype "passive"))
      (node (ref "R15") (pin "1") (pinfunction "1_1") (pintype "passive"))
      (node (ref "R16") (pin "1") (pinfunction "1_1") (pintype "passive"))
      (node (ref "R17") (pin "1") (pinfunction "1_1") (pintype "passive"))
      (node (ref "U1") (pin "21") (pinfunction "AGND_21") (pintype "bidirectional"))
      (node (ref "U1") (pin "3") (pinfunction "GND_3") (pintype "bidirectional"))
      (node (ref "U1") (pin "5") (pinfunction "GND_5") (pintype "bidirectional"))
      (node (ref "U2") (pin "10") (pinfunction "RES_10") (pintype "bidirectional"))
      (node (ref "U2") (pin "12") (pinfunction "GND_12") (pintype "bidirectional"))
      (node (ref "U2") (pin "5") (pinfunction "GND_5") (pintype "bidirectional"))
      (node (ref "U3") (pin "5") (pinfunction "GND_5") (pintype "bidirectional"))
      (node (ref "X1") (pin "3") (pinfunction "3_3") (pintype "passive"))
      (node (ref "X1") (pin "6") (pinfunction "6_6") (pintype "passive"))
      (node (ref "X1") (pin "7") (pinfunction "7_7") (pintype "passive"))
      (node (ref "X1") (pin "8") (pinfunction "8_8") (pintype "passive"))
      (node (ref "X3") (pin "3") (pinfunction "3_3") (pintype "passive"))
      (node (ref "X3") (pin "6") (pinfunction "6_6") (pintype "passive"))
      (node (ref "X3") (pin "7") (pinfunction "7_7") (pintype "passive"))
      (node (ref "X3") (pin "8") (pinfunction "8_8") (pintype "passive"))
      (node (ref "Y1") (pin "2") (pinfunction "2_2") (pintype "passive"))
    )
    (net (code "41") (name "Net-(C1-Pad1)") (class "Default")
      (node (ref "C1") (pin "1") (pinfunction "1_1") (pintype "passive"))
      (node (ref "J2") (pin "1") (pinfunction "1_1") (pintype "passive"))
    )
    (net (code "42") (name "Net-(C36-Pad2)") (class "Default")
      (node (ref "C36") (pin "2") (pinfunction "2_2") (pintype "passive"))
      (node (ref "R17") (pin "2") (pinfunction "2_2") (pintype "passive"))
    )
    (net (code "43") (name "Net-(D7-DO)") (class "Default")
      (node (ref "D7") (pin "2") (pinfunction "DO_2") (pintype "bidirectional"))
      (node (ref "D8") (pin "4") (pinfunction "DI_4") (pintype "bidirectional"))
    )
    (net (code "44") (name "Net-(D8-DO)") (class "Default")
      (node (ref "D8") (pin "2") (pinfunction "DO_2") (pintype "bidirectional"))
      (node (ref "D9") (pin "4") (pinfunction "DI_4") (pintype "bidirectional"))
    )
    (net (code "45") (name "Net-(D10-DI)") (class "Default")
      (node (ref "D10") (pin "4") (pinfunction "DI_4") (pintype "bidirectional"))
      (node (ref "D9") (pin "2") (pinfunction "DO_2") (pintype "bidirectional"))
    )
    (net (code "46") (name "Net-(D10-DO)") (class "Default")
      (node (ref "D10") (pin "2") (pinfunction "DO_2") (pintype "bidirectional"))
      (node (ref "D11") (pin "4") (pinfunction "DI_4") (pintype "bidirectional"))
    )
    (net (code "47") (name "Net-(D11-DO)") (class "Default")
      (node (ref "D11") (pin "2") (pinfunction "DO_2") (pintype "bidirectional"))
      (node (ref "D12") (pin "4") (pinfunction "DI_4") (pintype "bidirectional"))
    )
    (net (code "48") (name "Net-(D12-DO)") (class "Default")
      (node (ref "D12") (pin "2") (pinfunction "DO_2") (pintype "bidirectional"))
      (node (ref "D13") (pin "4") (pinfunction "DI_4") (pintype "bidirectional"))
    )
    (net (code "49") (name "Net-(D13-DO)") (class "Default")
      (node (ref "D13") (pin "2") (pinfunction "DO_2") (pintype "bidirectional"))
      (node (ref "D14") (pin "4") (pinfunction "DI_4") (pintype "bidirectional"))
    )
    (net (code "50") (name "Net-(D14-DO)") (class "Default")
      (node (ref "D14") (pin "2") (pinfunction "DO_2") (pintype "bidirectional"))
      (node (ref "D15") (pin "4") (pinfunction "DI_4") (pintype "bidirectional"))
    )
    (net (code "51") (name "Net-(D15-DO)") (class "Default")
      (node (ref "D15") (pin "2") (pinfunction "DO_2") (pintype "bidirectional"))
      (node (ref "D16") (pin "4") (pinfunction "DI_4") (pintype "bidirectional"))
    )
    (net (code "52") (name "Net-(D16-DO)") (class "Default")
      (node (ref "D16") (pin "2") (pinfunction "DO_2") (pintype "bidirectional"))
      (node (ref "D17") (pin "4") (pinfunction "DI_4") (pintype "bidirectional"))
    )
    (net (code "53") (name "Net-(D17-DO)") (class "Default")
      (node (ref "D17") (pin "2") (pinfunction "DO_2") (pintype "bidirectional"))
      (node (ref "D18") (pin "4") (pinfunction "DI_4") (pintype "bidirectional"))
    )
    (net (code "54") (name "Net-(J3-Pad1)") (class "Default")
      (node (ref "J3") (pin "1") (pinfunction "1_1") (pintype "passive"))
      (node (ref "R2") (pin "2") (pinfunction "2_2") (pintype "passive"))
    )
    (net (code "55") (name "Net-(J4-Pad1)") (class "Default")
      (node (ref "J4") (pin "1") (pinfunction "1_1") (pintype "passive"))
      (node (ref "R3") (pin "2") (pinfunction "2_2") (pintype "passive"))
    )
    (net (code "56") (name "Net-(J5-Pad1)") (class "Default")
      (node (ref "J5") (pin "1") (pinfunction "1_1") (pintype "passive"))
      (node (ref "R4") (pin "2") (pinfunction "2_2") (pintype "passive"))
    )
    (net (code "57") (name "Net-(Q1-D)") (class "Default")
      (node (ref "Q1") (pin "3") (pinfunction "D_3") (pintype "bidirectional"))
      (node (ref "R2") (pin "1") (pinfunction "1_1") (pintype "passive"))
    )
    (net (code "58") (name "Net-(Q2-D)") (class "Default")
      (node (ref "Q2") (pin "3") (pinfunction "D_3") (pintype "bidirectional"))
      (node (ref "R3") (pin "1") (pinfunction "1_1") (pintype "passive"))
    )
    (net (code "59") (name "Net-(Q3-D)") (class "Default")
      (node (ref "Q3") (pin "3") (pinfunction "D_3") (pintype "bidirectional"))
      (node (ref "R4") (pin "1") (pinfunction "1_1") (pintype "passive"))
    )
    (net (code "60") (name "Net-(U1-PB6(XTAL1{slash}TOSC1))") (class "Default")
      (node (ref "U1") (pin "7") (pinfunction "PB6(XTAL1/TOSC1)_7") (pintype "bidirectional"))
      (node (ref "Y1") (pin "1") (pinfunction "1_1") (pintype "passive"))
    )
    (net (code "61") (name "Net-(U1-PB7(XTAL2{slash}TOSC2))") (class "Default")
      (node (ref "U1") (pin "8") (pinfunction "PB7(XTAL2/TOSC2)_8") (pintype "bidirectional"))
      (node (ref "Y1") (pin "3") (pinfunction "3_3") (pintype "passive"))
    )
    (net (code "62") (name "Net-(U3-A)") (class "Default")
      (node (ref "R11") (pin "1") (pinfunction "1_1") (pintype "passive"))
      (node (ref "U3") (pin "6") (pinfunction "A_6") (pintype "bidirectional"))
      (node (ref "X1") (pin "2") (pinfunction "2_2") (pintype "passive"))
      (node (ref "X3") (pin "2") (pinfunction "2_2") (pintype "passive"))
    )
    (net (code "63") (name "Net-(U3-B)") (class "Default")
      (node (ref "R11") (pin "2") (pinfunction "2_2") (pintype "passive"))
      (node (ref "U3") (pin "7") (pinfunction "B_7") (pintype "bidirectional"))
      (node (ref "X1") (pin "1") (pinfunction "1_1") (pintype "passive"))
      (node (ref "X3") (pin "1") (pinfunction "1_1") (pintype "passive"))
    )
    (net (code "64") (name "Net-(U3-DI)") (class "Default")
      (node (ref "R13") (pin "2") (pinfunction "2_2") (pintype "passive"))
      (node (ref "U3") (pin "4") (pinfunction "DI_4") (pintype "bidirectional"))
    )
    (net (code "65") (name "Net-(U3-RO)") (class "Default")
      (node (ref "R12") (pin "2") (pinfunction "2_2") (pintype "passive"))
      (node (ref "U3") (pin "1") (pinfunction "RO_1") (pintype "bidirectional"))
    )
    (net (code "66") (name "unconnected-(D18-DO-Pad2)") (class "Default")
      (node (ref "D18") (pin "2") (pinfunction "DO_2") (pintype "bidirectional"))
    )
    (net (code "67") (name "unconnected-(J2-Pad5)") (class "Default")
      (node (ref "J2") (pin "5") (pinfunction "5_5") (pintype "passive"))
    )
    (net (code "68") (name "unconnected-(U2-ADC1-Pad16)") (class "Default")
      (node (ref "U2") (pin "16") (pinfunction "ADC1_16") (pintype "bidirectional"))
    )
    (net (code "69") (name "unconnected-(U2-ADC2-Pad15)") (class "Default")
      (node (ref "U2") (pin "15") (pinfunction "ADC2_15") (pintype "bidirectional"))
    )
    (net (code "70") (name "unconnected-(U2-ADC3-Pad13)") (class "Default")
      (node (ref "U2") (pin "13") (pinfunction "ADC3_13") (pintype "bidirectional"))
    )
  )
)
